# 14.net
KiCad netlist of a schematic drawn in Altium Designer
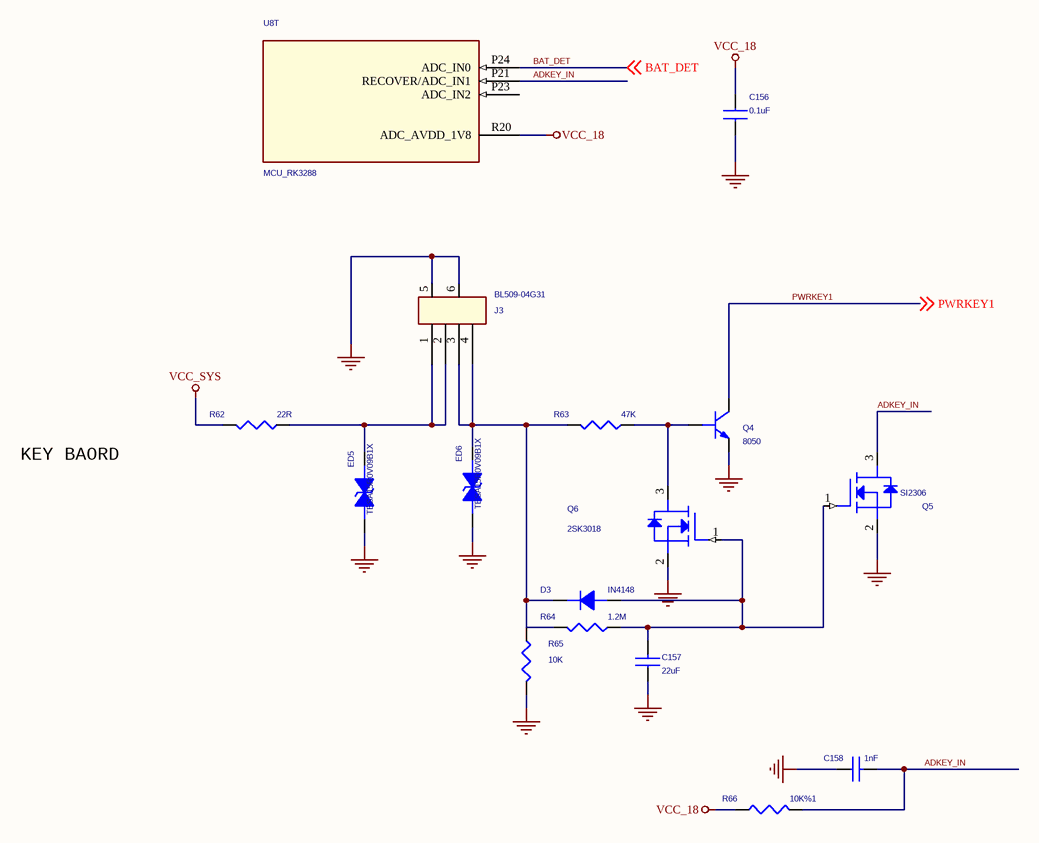
[diagram p0: 14.SchDoc]

(export (version "E")
  (design (tool "Eeschema 10.0.6"))
  (components
    (comp (ref "C156")
      (value "0.1uF")
      (footprint "C0603")
      (description "贴片电容")
      (libsource (lib "*") (part "CAP NP_Dup3"))
    )
    (comp (ref "C157")
      (value "22uF")
      (footprint "C0402")
      (description "RoHS CHIP CAP 4.7uF 25V +10/-10% 16V X7R")
      (libsource (lib "*") (part "CAP NP_Dup2"))
    )
    (comp (ref "C158")
      (value "1nF")
      (footprint "C0402")
      (description "RoHS CHIP CAP 1nF +10/-10% X7R")
      (libsource (lib "*") (part "CAP NP_Dup2"))
    )
    (comp (ref "D3")
      (value "IN4148")
      (footprint "SOD323")
      (description "Diode,Schottky,1N5819HW,40V,500mA,450mV,SOD-323")
      (libsource (lib "*") (part "DIODE_Dup1"))
    )
    (comp (ref "ED5")
      (value "TESA15R0V09B1X")
      (footprint "E0402N")
      (description "ESD Component,5V,30P,SMD,0402")
      (libsource (lib "*") (part "TVS"))
    )
    (comp (ref "ED6")
      (value "TESA15R0V09B1X")
      (footprint "E0402N")
      (description "ESD Component,5V,30P,SMD,0402")
      (libsource (lib "*") (part "TVS"))
    )
    (comp (ref "J3") (value "BL509-04G31") (footprint "BL509-04G31") (libsource (lib "*") (part "CON4_0")))
    (comp (ref "Q4")
      (value "8050")
      (footprint "SOT23")
      (description "Trans NPN,SS8050,25V,1500mA,10~60@Vce=1V,Ic=500mA, SOT-23")
      (libsource (lib "*") (part "40852_1"))
    )
    (comp (ref "Q5")
      (value "SI2306")
      (footprint "SOT23")
      (description "MOSFET-N,WNM2021 ,20V,+/-8V,0.8A,300m Ohm@Vgs=4.5V,SOT23")
      (libsource (lib "*") (part "MOSFET N"))
    )
    (comp (ref "Q6")
      (value "2SK3018")
      (footprint "SOT23")
      (description "MOSFET-N,WNM2021 ,20V,+/-8V,0.8A,300m Ohm@Vgs=4.5V,SOT23")
      (libsource (lib "*") (part "MOSFET N"))
    )
    (comp (ref "R62")
      (value "22R")
      (footprint "R0402")
      (description "ROHS CHIP RES 51K 1/16W ±5%")
      (libsource (lib "*") (part "RESISTOR_Dup1"))
    )
    (comp (ref "R63")
      (value "47K")
      (footprint "R0402")
      (description "ROHS CHIP RES 51K 1/16W ±5%")
      (libsource (lib "*") (part "RESISTOR_Dup1"))
    )
    (comp (ref "R64")
      (value "1.2M")
      (footprint "R0402")
      (description "ROHS CHIP RES 51K 1/16W ±5%")
      (libsource (lib "*") (part "RESISTOR_Dup1"))
    )
    (comp (ref "R65")
      (value "10K")
      (footprint "R0402")
      (description "ROHS CHIP RES 51K 1/16W ±5%")
      (libsource (lib "*") (part "RESISTOR_Dup1"))
    )
    (comp (ref "R66")
      (value "10K%1")
      (footprint "R0402")
      (description "ROHS CHIP RES 10K 1/16W +/-1%")
      (libsource (lib "*") (part "RESISTOR_Dup1"))
    )
    (comp (ref "U8")
      (value "MCU_RK3288")
      (footprint "BGA453-19X19")
      (libsource (lib "*") (part "MCU_RK3288_3"))
    )
  )
  (nets
    (net (code "1") (name "/ADKEY_IN") (class "Default")
      (node (ref "C158") (pin "2") (pinfunction "2_2") (pintype "passive"))
      (node (ref "Q5") (pin "3") (pinfunction "DRAIN_3") (pintype "passive"))
      (node (ref "R66") (pin "2") (pinfunction "2_2") (pintype "passive"))
      (node (ref "U8") (pin "P21") (pinfunction "RECOVER/ADC_IN1_P21") (pintype "input"))
    )
    (net (code "2") (name "BAT_DET") (class "Default")
      (node (ref "U8") (pin "P24") (pinfunction "ADC_IN0_P24") (pintype "input"))
    )
    (net (code "3") (name "GND") (class "Default")
      (node (ref "C156") (pin "1") (pinfunction "1_1") (pintype "passive"))
      (node (ref "C157") (pin "1") (pinfunction "1_1") (pintype "passive"))
      (node (ref "C158") (pin "1") (pinfunction "1_1") (pintype "passive"))
      (node (ref "ED5") (pin "2") (pinfunction "2_2") (pintype "passive"))
      (node (ref "ED6") (pin "2") (pinfunction "2_2") (pintype "passive"))
      (node (ref "J3") (pin "5") (pinfunction "5_5") (pintype "passive"))
      (node (ref "J3") (pin "6") (pinfunction "6_6") (pintype "passive"))
      (node (ref "Q4") (pin "2") (pinfunction "E_2") (pintype "passive"))
      (node (ref "Q5") (pin "2") (pinfunction "SOURCE_2") (pintype "passive"))
      (node (ref "Q6") (pin "2") (pinfunction "SOURCE_2") (pintype "passive"))
      (node (ref "R65") (pin "2") (pinfunction "2_2") (pintype "passive"))
    )
    (net (code "4") (name "Net-(D3-A)") (class "Default")
      (node (ref "C157") (pin "2") (pinfunction "2_2") (pintype "passive"))
      (node (ref "D3") (pin "1") (pinfunction "A_1") (pintype "passive"))
      (node (ref "Q5") (pin "1") (pinfunction "GATE_1") (pintype "input"))
      (node (ref "Q6") (pin "1") (pinfunction "GATE_1") (pintype "input"))
      (node (ref "R64") (pin "1") (pinfunction "1_1") (pintype "passive"))
    )
    (net (code "5") (name "Net-(D3-K)") (class "Default")
      (node (ref "D3") (pin "2") (pinfunction "K_2") (pintype "passive"))
      (node (ref "ED6") (pin "1") (pinfunction "1_1") (pintype "passive"))
      (node (ref "J3") (pin "3") (pinfunction "3_3") (pintype "passive"))
      (node (ref "J3") (pin "4") (pinfunction "4_4") (pintype "passive"))
      (node (ref "R63") (pin "2") (pinfunction "2_2") (pintype "passive"))
      (node (ref "R64") (pin "2") (pinfunction "2_2") (pintype "passive"))
      (node (ref "R65") (pin "1") (pinfunction "1_1") (pintype "passive"))
    )
    (net (code "6") (name "Net-(ED5-Pad1)") (class "Default")
      (node (ref "ED5") (pin "1") (pinfunction "1_1") (pintype "passive"))
      (node (ref "J3") (pin "1") (pinfunction "1_1") (pintype "passive"))
      (node (ref "J3") (pin "2") (pinfunction "2_2") (pintype "passive"))
      (node (ref "R62") (pin "1") (pinfunction "1_1") (pintype "passive"))
    )
    (net (code "7") (name "Net-(Q4-B)") (class "Default")
      (node (ref "Q4") (pin "1") (pinfunction "B_1") (pintype "passive"))
      (node (ref "Q6") (pin "3") (pinfunction "DRAIN_3") (pintype "passive"))
      (node (ref "R63") (pin "1") (pinfunction "1_1") (pintype "passive"))
    )
    (net (code "8") (name "PWRKEY1") (class "Default")
      (node (ref "Q4") (pin "3") (pinfunction "C_3") (pintype "passive"))
    )
    (net (code "9") (name "VCC_18") (class "Default")
      (node (ref "C156") (pin "2") (pinfunction "2_2") (pintype "passive"))
      (node (ref "R66") (pin "1") (pinfunction "1_1") (pintype "passive"))
      (node (ref "U8") (pin "R20") (pinfunction "ADC_AVDD_1V8_R20") (pintype "power_in"))
    )
    (net (code "10") (name "VCC_SYS") (class "Default")
      (node (ref "R62") (pin "2") (pinfunction "2_2") (pintype "passive"))
    )
    (net (code "11") (name "unconnected-(U8T-ADC_IN2-PadP23)") (class "Default")
      (node (ref "U8") (pin "P23") (pinfunction "ADC_IN2_P23") (pintype "input"))
    )
  )
)
